# Schematic_tema_tsc_v23.net
KiCad netlist of a schematic drawn in EAGLE
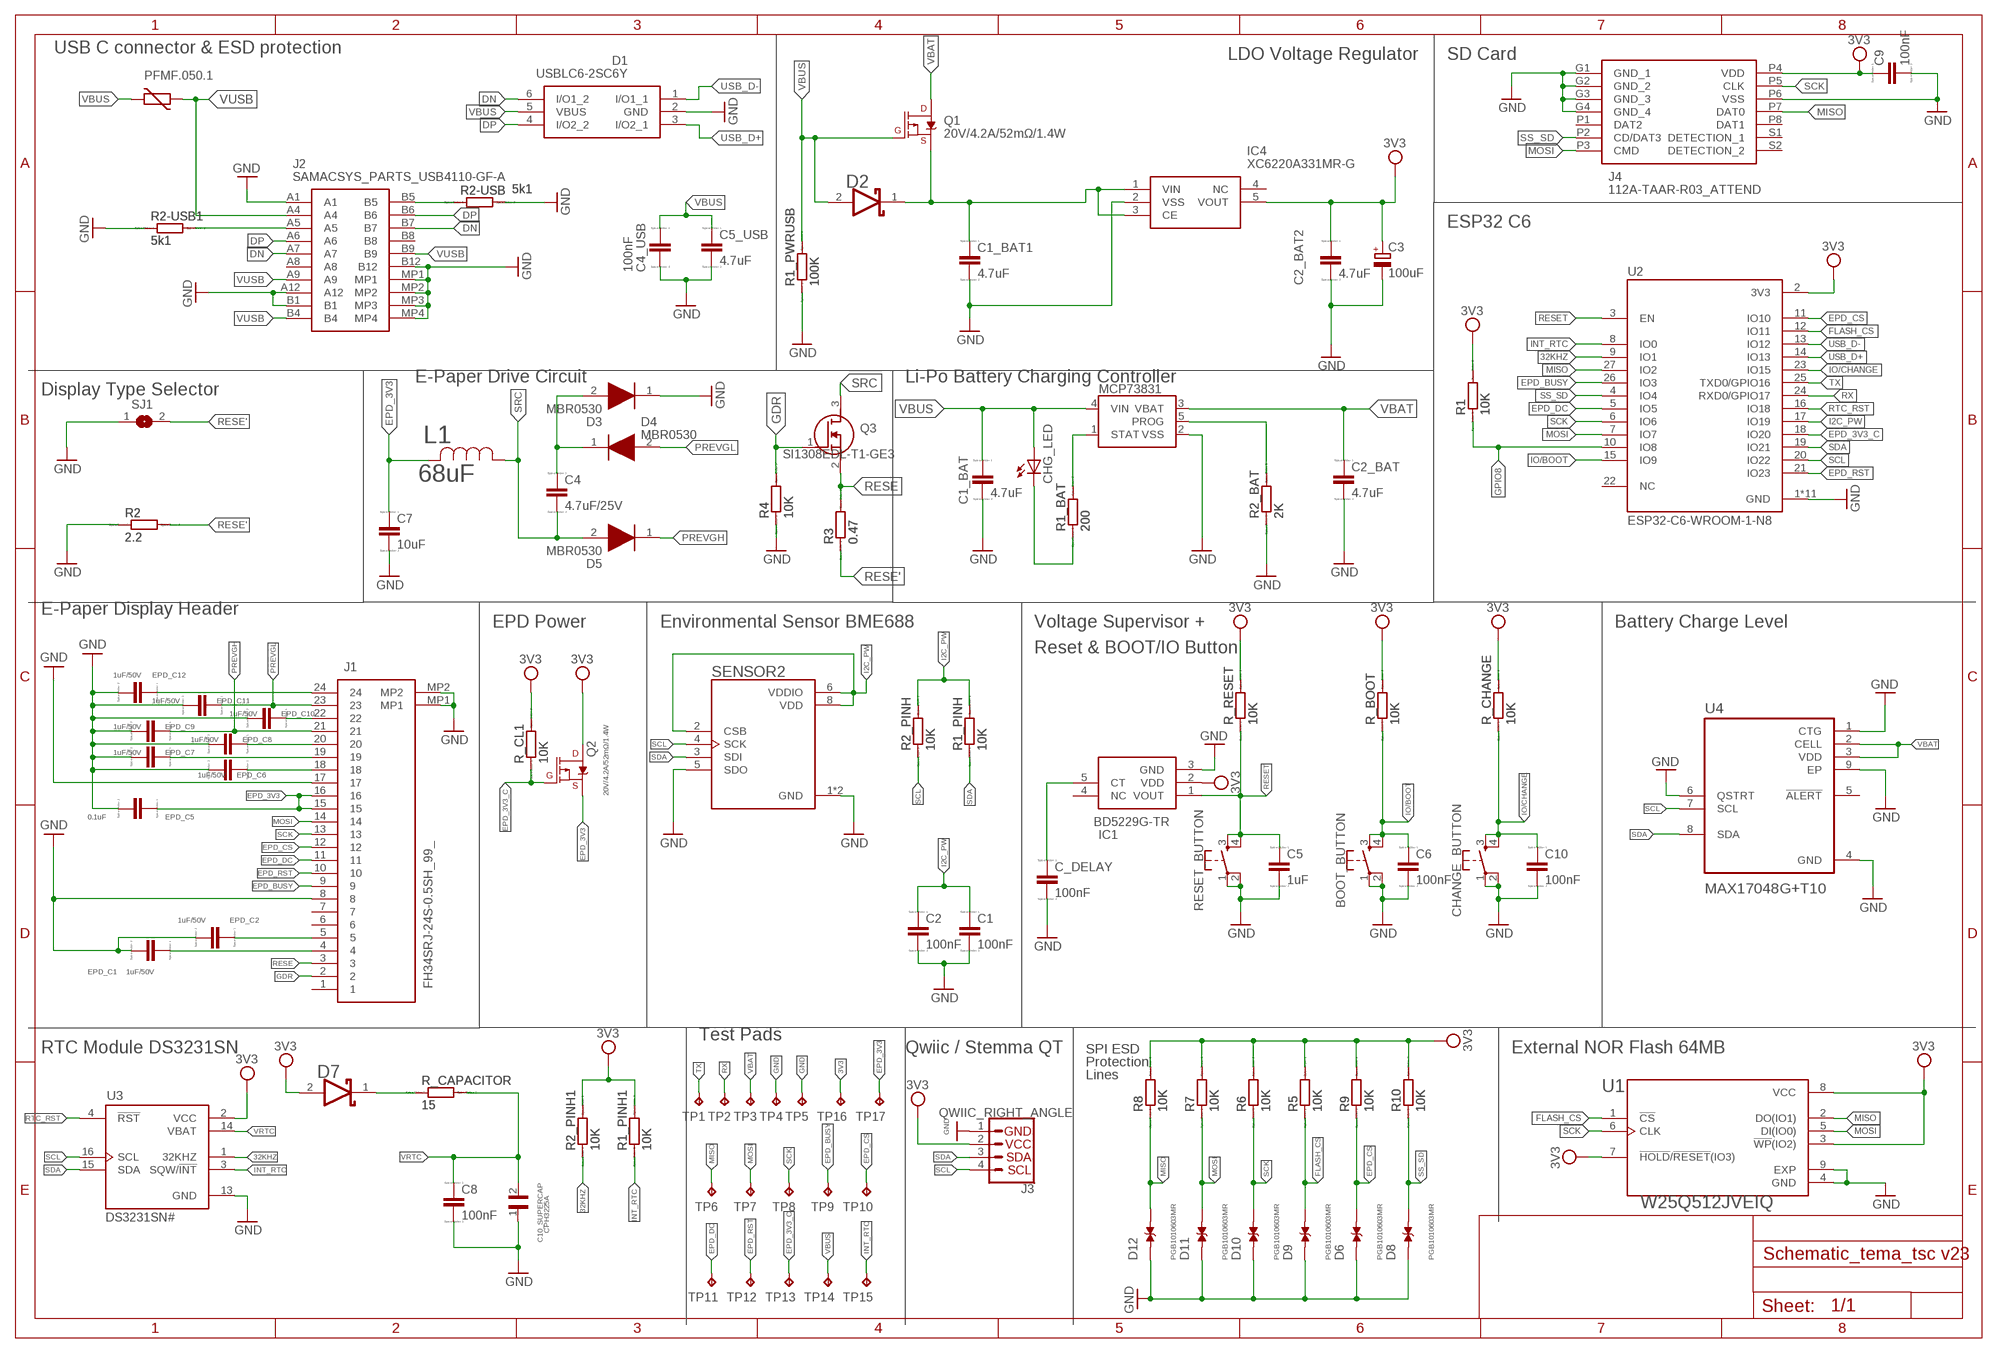
[diagram p0: schematic, sheet 1]

(export (version "E")
  (design (tool "Eeschema 10.0.6"))
  (components
    (comp (ref "BOOT_BUTTON")
      (value "BUTTON_CUSYOMV1")
      (footprint "eagle-import:MYBUTTON")
      (libsource (lib "eagle-import") (part "BUTTON_CUSYOMV1"))
    )
    (comp (ref "C1")
      (value "100nF")
      (footprint "eagle-import:EAGLE-LTSPICE_C0402")
      (libsource (lib "eagle-import") (part "EAGLE-LTSPICE_CC0402"))
    )
    (comp (ref "C1_BAT")
      (value "4.7uF")
      (footprint "eagle-import:EAGLE-LTSPICE_C0402")
      (libsource (lib "eagle-import") (part "EAGLE-LTSPICE_CC0402"))
    )
    (comp (ref "C1_BAT1")
      (value "4.7uF")
      (footprint "eagle-import:EAGLE-LTSPICE_C0402")
      (libsource (lib "eagle-import") (part "EAGLE-LTSPICE_CC0402"))
    )
    (comp (ref "C2")
      (value "100nF")
      (footprint "eagle-import:EAGLE-LTSPICE_C0402")
      (libsource (lib "eagle-import") (part "EAGLE-LTSPICE_CC0402"))
    )
    (comp (ref "C2_BAT")
      (value "4.7uF")
      (footprint "eagle-import:EAGLE-LTSPICE_C0402")
      (libsource (lib "eagle-import") (part "EAGLE-LTSPICE_CC0402"))
    )
    (comp (ref "C2_BAT2")
      (value "4.7uF")
      (footprint "eagle-import:EAGLE-LTSPICE_C0402")
      (libsource (lib "eagle-import") (part "EAGLE-LTSPICE_CC0402"))
    )
    (comp (ref "C3")
      (value "100uF")
      (footprint "eagle-import:RCL_CT3528")
      (libsource (lib "eagle-import") (part "RCL_CPOL-EUCT3528"))
    )
    (comp (ref "C4")
      (value "4.7uF/25V")
      (footprint "eagle-import:EAGLE-LTSPICE_C0402")
      (libsource (lib "eagle-import") (part "EAGLE-LTSPICE_CC0402"))
    )
    (comp (ref "C4_USB")
      (value "100nF")
      (footprint "eagle-import:EAGLE-LTSPICE_C0402")
      (libsource (lib "eagle-import") (part "EAGLE-LTSPICE_CC0402"))
    )
    (comp (ref "C5")
      (value "1uF")
      (footprint "eagle-import:EAGLE-LTSPICE_C0402")
      (libsource (lib "eagle-import") (part "EAGLE-LTSPICE_CC0402"))
    )
    (comp (ref "C5_USB")
      (value "4.7uF")
      (footprint "eagle-import:EAGLE-LTSPICE_C0402")
      (libsource (lib "eagle-import") (part "EAGLE-LTSPICE_CC0402"))
    )
    (comp (ref "C6")
      (value "100nF")
      (footprint "eagle-import:EAGLE-LTSPICE_C0402")
      (libsource (lib "eagle-import") (part "EAGLE-LTSPICE_CC0402"))
    )
    (comp (ref "C7")
      (value "10uF")
      (footprint "eagle-import:EAGLE-LTSPICE_C0402")
      (libsource (lib "eagle-import") (part "EAGLE-LTSPICE_CC0402"))
    )
    (comp (ref "C8")
      (value "100nF")
      (footprint "eagle-import:EAGLE-LTSPICE_C0402")
      (libsource (lib "eagle-import") (part "EAGLE-LTSPICE_CC0402"))
    )
    (comp (ref "C9")
      (value "100nF")
      (footprint "eagle-import:EAGLE-LTSPICE_C0402")
      (libsource (lib "eagle-import") (part "EAGLE-LTSPICE_CC0402"))
    )
    (comp (ref "C10")
      (value "100nF")
      (footprint "eagle-import:EAGLE-LTSPICE_C0402")
      (libsource (lib "eagle-import") (part "EAGLE-LTSPICE_CC0402"))
    )
    (comp (ref "C10_SUPERCAP")
      (value "CPH3225A")
      (footprint "eagle-import:CAPCP3225X100N")
      (fields (field (name "MF") "Seiko Instruments"))
      (libsource (lib "eagle-import") (part "CPH3225A"))
    )
    (comp (ref "CHANGE_BUTTON")
      (value "BUTTON_CUSYOMV1")
      (footprint "eagle-import:MYBUTTON")
      (libsource (lib "eagle-import") (part "BUTTON_CUSYOMV1"))
    )
    (comp (ref "CHG_LED")
      (value "ADAFRUIT_LEDCHIP-LED0603")
      (footprint "eagle-import:ADAFRUIT_CHIP-LED0603")
      (libsource (lib "eagle-import") (part "ADAFRUIT_LEDCHIP-LED0603"))
    )
    (comp (ref "C_DELAY")
      (value "100nF")
      (footprint "eagle-import:EAGLE-LTSPICE_C0402")
      (libsource (lib "eagle-import") (part "EAGLE-LTSPICE_CC0402"))
    )
    (comp (ref "D1")
      (value "USBLC6-2SC6Y")
      (footprint "eagle-import:SOT95P280X145-6N")
      (fields (field (name "MF") "STMicroelectronics"))
      (libsource (lib "eagle-import") (part "USBLC6-2SC6Y"))
    )
    (comp (ref "D2")
      (value "ESP32_WROVER_AVX---SD0805S020S1R0_AVX_SD0805S020S1R0_0_0AVX_SD0805S020S1R0_0_0")
      (footprint "eagle-import:ESP32_WROVER_AVX---SD0805S020S1R0_AVX_SD0805S020S1R0_0")
      (fields
        (field (name "DIGIKEY_PART_NUMBER") "478-7800-1-ND")
        (field (name "MF") "AVX")
        (field (name "MOUSER_PART_NUMBER") "581-SD0805S020S1R0")
      )
      (libsource (lib "eagle-import") (part "ESP32_WROVER_AVX---SD0805S020S1R0_AVX_SD0805S020S1R0_0_0AVX_SD0805S020S1R0_0_0"))
    )
    (comp (ref "D3")
      (value "MBR0530")
      (footprint "eagle-import:SOD3716X135N")
      (fields (field (name "MF") "ON Semiconductor"))
      (libsource (lib "eagle-import") (part "MBR0530"))
    )
    (comp (ref "D4")
      (value "MBR0530")
      (footprint "eagle-import:SOD3716X135N")
      (fields (field (name "MF") "ON Semiconductor"))
      (libsource (lib "eagle-import") (part "MBR0530"))
    )
    (comp (ref "D5")
      (value "MBR0530")
      (footprint "eagle-import:SOD3716X135N")
      (fields (field (name "MF") "ON Semiconductor"))
      (libsource (lib "eagle-import") (part "MBR0530"))
    )
    (comp (ref "D6")
      (value "PGB1010603MR")
      (footprint "eagle-import:DIOC1608X36N")
      (fields (field (name "MF") "Littelfuse Inc."))
      (libsource (lib "eagle-import") (part "PGB1010603MR"))
    )
    (comp (ref "D7")
      (value "ESP32_WROVER_AVX---SD0805S020S1R0_AVX_SD0805S020S1R0_0_0AVX_SD0805S020S1R0_0_0")
      (footprint "eagle-import:ESP32_WROVER_AVX---SD0805S020S1R0_AVX_SD0805S020S1R0_0")
      (fields
        (field (name "DIGIKEY_PART_NUMBER") "478-7800-1-ND")
        (field (name "MF") "AVX")
        (field (name "MOUSER_PART_NUMBER") "581-SD0805S020S1R0")
      )
      (libsource (lib "eagle-import") (part "ESP32_WROVER_AVX---SD0805S020S1R0_AVX_SD0805S020S1R0_0_0AVX_SD0805S020S1R0_0_0"))
    )
    (comp (ref "D8")
      (value "PGB1010603MR")
      (footprint "eagle-import:DIOC1608X36N")
      (fields (field (name "MF") "Littelfuse Inc."))
      (libsource (lib "eagle-import") (part "PGB1010603MR"))
    )
    (comp (ref "D9")
      (value "PGB1010603MR")
      (footprint "eagle-import:DIOC1608X36N")
      (fields (field (name "MF") "Littelfuse Inc."))
      (libsource (lib "eagle-import") (part "PGB1010603MR"))
    )
    (comp (ref "D10")
      (value "PGB1010603MR")
      (footprint "eagle-import:DIOC1608X36N")
      (fields (field (name "MF") "Littelfuse Inc."))
      (libsource (lib "eagle-import") (part "PGB1010603MR"))
    )
    (comp (ref "D11")
      (value "PGB1010603MR")
      (footprint "eagle-import:DIOC1608X36N")
      (fields (field (name "MF") "Littelfuse Inc."))
      (libsource (lib "eagle-import") (part "PGB1010603MR"))
    )
    (comp (ref "D12")
      (value "PGB1010603MR")
      (footprint "eagle-import:DIOC1608X36N")
      (fields (field (name "MF") "Littelfuse Inc."))
      (libsource (lib "eagle-import") (part "PGB1010603MR"))
    )
    (comp (ref "EPD_C1")
      (value "1uF/50V")
      (footprint "eagle-import:EAGLE-LTSPICE_C0402")
      (libsource (lib "eagle-import") (part "EAGLE-LTSPICE_CC0402"))
    )
    (comp (ref "EPD_C2")
      (value "1uF/50V")
      (footprint "eagle-import:EAGLE-LTSPICE_C0402")
      (libsource (lib "eagle-import") (part "EAGLE-LTSPICE_CC0402"))
    )
    (comp (ref "EPD_C5")
      (value "0.1uF")
      (footprint "eagle-import:EAGLE-LTSPICE_C0402")
      (libsource (lib "eagle-import") (part "EAGLE-LTSPICE_CC0402"))
    )
    (comp (ref "EPD_C6")
      (value "1uF/50V")
      (footprint "eagle-import:EAGLE-LTSPICE_C0402")
      (libsource (lib "eagle-import") (part "EAGLE-LTSPICE_CC0402"))
    )
    (comp (ref "EPD_C7")
      (value "1uF/50V")
      (footprint "eagle-import:EAGLE-LTSPICE_C0402")
      (libsource (lib "eagle-import") (part "EAGLE-LTSPICE_CC0402"))
    )
    (comp (ref "EPD_C8")
      (value "1uF/50V")
      (footprint "eagle-import:EAGLE-LTSPICE_C0402")
      (libsource (lib "eagle-import") (part "EAGLE-LTSPICE_CC0402"))
    )
    (comp (ref "EPD_C9")
      (value "1uF/50V")
      (footprint "eagle-import:EAGLE-LTSPICE_C0402")
      (libsource (lib "eagle-import") (part "EAGLE-LTSPICE_CC0402"))
    )
    (comp (ref "EPD_C10")
      (value "1uF/50V")
      (footprint "eagle-import:EAGLE-LTSPICE_C0402")
      (libsource (lib "eagle-import") (part "EAGLE-LTSPICE_CC0402"))
    )
    (comp (ref "EPD_C11")
      (value "1uF/50V")
      (footprint "eagle-import:EAGLE-LTSPICE_C0402")
      (libsource (lib "eagle-import") (part "EAGLE-LTSPICE_CC0402"))
    )
    (comp (ref "EPD_C12")
      (value "1uF/50V")
      (footprint "eagle-import:EAGLE-LTSPICE_C0402")
      (libsource (lib "eagle-import") (part "EAGLE-LTSPICE_CC0402"))
    )
    (comp (ref "IC1")
      (value "BD5229G-TR")
      (footprint "eagle-import:SOT95P280X125-5N")
      (fields (field (name "MOUSER_PART_NUMBER") "755-BD5229G-TR"))
      (libsource (lib "eagle-import") (part "BD5229G-TR"))
    )
    (comp (ref "IC4")
      (value "XC6220A331MR-G")
      (footprint "eagle-import:SOT95P280X120-5N")
      (fields (field (name "MOUSER_PART_NUMBER") "865-XC6220A331MR-G"))
      (libsource (lib "eagle-import") (part "XC6220A331MR-G"))
    )
    (comp (ref "J1")
      (value "FH34SRJ-24S-0.5SH_99_")
      (footprint "eagle-import:FH34SRJ24S05SH99")
      (fields
        (field (name "MANUFACTURER_PART_NUMBER") "FH34SRJ-24S-0.5SH(99)")
        (field (name "MOUSER_PART_NUMBER") "798-FH34SRJ24S05SH99")
      )
      (libsource (lib "eagle-import") (part "FH34SRJ-24S-0.5SH_99_"))
    )
    (comp (ref "J2")
      (value "SAMACSYS_PARTS_USB4110-GF-A")
      (footprint "eagle-import:SAMACSYS_PARTS_USB4110GFA")
      (fields
        (field (name "MANUFACTURER_PART_NUMBER") "USB4110-GF-A")
        (field (name "MOUSER_PART_NUMBER") "640-USB4110-GF-A")
      )
      (libsource (lib "eagle-import") (part "SAMACSYS_PARTS_USB4110-GF-A"))
    )
    (comp (ref "J3")
      (value "QWIIC_RIGHT_ANGLE")
      (footprint "eagle-import:JST04_1MM_RA")
      (libsource (lib "eagle-import") (part "QWIIC_CONNECTORJS-1MM"))
    )
    (comp (ref "J4")
      (value "112A-TAAR-R03_ATTEND")
      (footprint "eagle-import:112ATAARR03ATTEND")
      (fields (field (name "MANUFACTURER_PART_NUMBER") "112A-TAAR-R03 ATTEND"))
      (libsource (lib "eagle-import") (part "112A-TAAR-R03_ATTEND"))
    )
    (comp (ref "L1")
      (value "68uF")
      (footprint "eagle-import:IND_4828-WE-TPC_WRE")
      (fields
        (field (name "MANUFACTURER_PART_NUMBER") "744043680")
        (field (name "COPYRIGHT") "Copyright (C) 2024 Ultra Librarian. All rights reserved.")
      )
      (libsource (lib "eagle-import") (part "744043680IND_4828-WE-TPC_WRE"))
    )
    (comp (ref "MCP73831")
      (value "ESP32_WROVER_SPARKFUN-IC-POWER_MCP73831")
      (footprint "eagle-import:ESP32_WROVER_SPARKFUN-IC-POWER_SOT23-5")
      (libsource (lib "eagle-import") (part "ESP32_WROVER_SPARKFUN-IC-POWER_MCP73831"))
    )
    (comp (ref "PFMF.050.1")
      (value "ESP32C6_VARISTORCN1812")
      (footprint "eagle-import:ESP32C6_VARISTOR_CT_CN1812")
      (libsource (lib "eagle-import") (part "ESP32C6_VARISTORCN1812"))
    )
    (comp (ref "Q1")
      (value "20V/4.2A/52mΩ/1.4W")
      (footprint "eagle-import:ESP32_WROVER_SPARKFUN-DISCRETESEMI_SOT23-3")
      (libsource (lib "eagle-import") (part "ESP32_WROVER_SPARKFUN-DISCRETESEMI_MOSFET_PCH-DMG2305UX-7"))
    )
    (comp (ref "Q2")
      (value "20V/4.2A/52mΩ/1.4W")
      (footprint "eagle-import:ESP32_WROVER_SPARKFUN-DISCRETESEMI_SOT23-3")
      (libsource (lib "eagle-import") (part "ESP32_WROVER_SPARKFUN-DISCRETESEMI_MOSFET_PCH-DMG2305UX-7"))
    )
    (comp (ref "Q3")
      (value "SI1308EDL-T1-GE3")
      (footprint "eagle-import:SOT65P210X110-3N")
      (fields (field (name "MF") "Vishay Siliconix"))
      (libsource (lib "eagle-import") (part "SI1308EDL-T1-GE3"))
    )
    (comp (ref "R1")
      (value "10K")
      (footprint "eagle-import:ESP32_WROVER_EAGLE-LTSPICE_R0402")
      (libsource (lib "eagle-import") (part "ESP32_WROVER_EAGLE-LTSPICE_RR0402"))
    )
    (comp (ref "R1_BAT")
      (value "200")
      (footprint "eagle-import:ESP32_WROVER_EAGLE-LTSPICE_R0402")
      (libsource (lib "eagle-import") (part "ESP32_WROVER_EAGLE-LTSPICE_RR0402"))
    )
    (comp (ref "R1_PINH")
      (value "10K")
      (footprint "eagle-import:ESP32_WROVER_EAGLE-LTSPICE_R0402")
      (libsource (lib "eagle-import") (part "ESP32_WROVER_EAGLE-LTSPICE_RR0402"))
    )
    (comp (ref "R1_PINH1")
      (value "10K")
      (footprint "eagle-import:ESP32_WROVER_EAGLE-LTSPICE_R0402")
      (libsource (lib "eagle-import") (part "ESP32_WROVER_EAGLE-LTSPICE_RR0402"))
    )
    (comp (ref "R1_PWRUSB")
      (value "100K")
      (footprint "eagle-import:ESP32_WROVER_EAGLE-LTSPICE_R0402")
      (libsource (lib "eagle-import") (part "ESP32_WROVER_EAGLE-LTSPICE_RR0402"))
    )
    (comp (ref "R2")
      (value "2.2")
      (footprint "eagle-import:ESP32_WROVER_EAGLE-LTSPICE_R0402")
      (libsource (lib "eagle-import") (part "ESP32_WROVER_EAGLE-LTSPICE_RR0402"))
    )
    (comp (ref "R2-USB")
      (value "5k1")
      (footprint "eagle-import:ESP32_WROVER_EAGLE-LTSPICE_R0402")
      (libsource (lib "eagle-import") (part "ESP32_WROVER_EAGLE-LTSPICE_RR0402"))
    )
    (comp (ref "R2-USB1")
      (value "5k1")
      (footprint "eagle-import:ESP32_WROVER_EAGLE-LTSPICE_R0402")
      (libsource (lib "eagle-import") (part "ESP32_WROVER_EAGLE-LTSPICE_RR0402"))
    )
    (comp (ref "R2_BAT")
      (value "2K")
      (footprint "eagle-import:ESP32_WROVER_EAGLE-LTSPICE_R0402")
      (libsource (lib "eagle-import") (part "ESP32_WROVER_EAGLE-LTSPICE_RR0402"))
    )
    (comp (ref "R2_PINH")
      (value "10K")
      (footprint "eagle-import:ESP32_WROVER_EAGLE-LTSPICE_R0402")
      (libsource (lib "eagle-import") (part "ESP32_WROVER_EAGLE-LTSPICE_RR0402"))
    )
    (comp (ref "R2_PINH1")
      (value "10K")
      (footprint "eagle-import:ESP32_WROVER_EAGLE-LTSPICE_R0402")
      (libsource (lib "eagle-import") (part "ESP32_WROVER_EAGLE-LTSPICE_RR0402"))
    )
    (comp (ref "R3")
      (value "0.47")
      (footprint "eagle-import:ESP32_WROVER_EAGLE-LTSPICE_R0402")
      (libsource (lib "eagle-import") (part "ESP32_WROVER_EAGLE-LTSPICE_RR0402"))
    )
    (comp (ref "R4")
      (value "10K")
      (footprint "eagle-import:ESP32_WROVER_EAGLE-LTSPICE_R0402")
      (libsource (lib "eagle-import") (part "ESP32_WROVER_EAGLE-LTSPICE_RR0402"))
    )
    (comp (ref "R5")
      (value "10K")
      (footprint "eagle-import:ESP32_WROVER_EAGLE-LTSPICE_R0402")
      (libsource (lib "eagle-import") (part "ESP32_WROVER_EAGLE-LTSPICE_RR0402"))
    )
    (comp (ref "R6")
      (value "10K")
      (footprint "eagle-import:ESP32_WROVER_EAGLE-LTSPICE_R0402")
      (libsource (lib "eagle-import") (part "ESP32_WROVER_EAGLE-LTSPICE_RR0402"))
    )
    (comp (ref "R7")
      (value "10K")
      (footprint "eagle-import:ESP32_WROVER_EAGLE-LTSPICE_R0402")
      (libsource (lib "eagle-import") (part "ESP32_WROVER_EAGLE-LTSPICE_RR0402"))
    )
    (comp (ref "R8")
      (value "10K")
      (footprint "eagle-import:ESP32_WROVER_EAGLE-LTSPICE_R0402")
      (libsource (lib "eagle-import") (part "ESP32_WROVER_EAGLE-LTSPICE_RR0402"))
    )
    (comp (ref "R9")
      (value "10K")
      (footprint "eagle-import:ESP32_WROVER_EAGLE-LTSPICE_R0402")
      (libsource (lib "eagle-import") (part "ESP32_WROVER_EAGLE-LTSPICE_RR0402"))
    )
    (comp (ref "R10")
      (value "10K")
      (footprint "eagle-import:ESP32_WROVER_EAGLE-LTSPICE_R0402")
      (libsource (lib "eagle-import") (part "ESP32_WROVER_EAGLE-LTSPICE_RR0402"))
    )
    (comp (ref "RESET_BUTTON")
      (value "BUTTON_CUSYOMV1")
      (footprint "eagle-import:MYBUTTON")
      (libsource (lib "eagle-import") (part "BUTTON_CUSYOMV1"))
    )
    (comp (ref "R_BOOT")
      (value "10K")
      (footprint "eagle-import:ESP32_WROVER_EAGLE-LTSPICE_R0402")
      (libsource (lib "eagle-import") (part "ESP32_WROVER_EAGLE-LTSPICE_RR0402"))
    )
    (comp (ref "R_CAPACITOR")
      (value "15")
      (footprint "eagle-import:ESP32_WROVER_EAGLE-LTSPICE_R0402")
      (libsource (lib "eagle-import") (part "ESP32_WROVER_EAGLE-LTSPICE_RR0402"))
    )
    (comp (ref "R_CHANGE")
      (value "10K")
      (footprint "eagle-import:ESP32_WROVER_EAGLE-LTSPICE_R0402")
      (libsource (lib "eagle-import") (part "ESP32_WROVER_EAGLE-LTSPICE_RR0402"))
    )
    (comp (ref "R_CL1")
      (value "10K")
      (footprint "eagle-import:ESP32_WROVER_EAGLE-LTSPICE_R0402")
      (libsource (lib "eagle-import") (part "ESP32_WROVER_EAGLE-LTSPICE_RR0402"))
    )
    (comp (ref "R_RESET")
      (value "10K")
      (footprint "eagle-import:ESP32_WROVER_EAGLE-LTSPICE_R0402")
      (libsource (lib "eagle-import") (part "ESP32_WROVER_EAGLE-LTSPICE_RR0402"))
    )
    (comp (ref "SENSOR2")
      (value "ESP32_WROVER_BME680_BME680")
      (footprint "eagle-import:ESP32_WROVER_BME680_PSON80P300X300X100-8N")
      (fields (field (name "MF") "Bosch Sensortec") (field (name "MP") "BME680"))
      (libsource (lib "eagle-import") (part "ESP32_WROVER_BME680_BME680"))
    )
    (comp (ref "SJ1") (value "SJ") (footprint "eagle-import:SJ") (libsource (lib "eagle-import") (part "SJ")))
    (comp (ref "TP1")
      (value "TPTP20R")
      (footprint "eagle-import:TP20R")
      (libsource (lib "eagle-import") (part "TPTP20R"))
    )
    (comp (ref "TP2")
      (value "TPTP20R")
      (footprint "eagle-import:TP20R")
      (libsource (lib "eagle-import") (part "TPTP20R"))
    )
    (comp (ref "TP3")
      (value "TPTP20R")
      (footprint "eagle-import:TP20R")
      (libsource (lib "eagle-import") (part "TPTP20R"))
    )
    (comp (ref "TP4")
      (value "TPTP20R")
      (footprint "eagle-import:TP20R")
      (libsource (lib "eagle-import") (part "TPTP20R"))
    )
    (comp (ref "TP5")
      (value "TPTP20R")
      (footprint "eagle-import:TP20R")
      (libsource (lib "eagle-import") (part "TPTP20R"))
    )
    (comp (ref "TP6")
      (value "TPTP20R")
      (footprint "eagle-import:TP20R")
      (libsource (lib "eagle-import") (part "TPTP20R"))
    )
    (comp (ref "TP7")
      (value "TPTP20R")
      (footprint "eagle-import:TP20R")
      (libsource (lib "eagle-import") (part "TPTP20R"))
    )
    (comp (ref "TP8")
      (value "TPTP20R")
      (footprint "eagle-import:TP20R")
      (libsource (lib "eagle-import") (part "TPTP20R"))
    )
    (comp (ref "TP9")
      (value "TPTP20R")
      (footprint "eagle-import:TP20R")
      (libsource (lib "eagle-import") (part "TPTP20R"))
    )
    (comp (ref "TP10")
      (value "TPTP20R")
      (footprint "eagle-import:TP20R")
      (libsource (lib "eagle-import") (part "TPTP20R"))
    )
    (comp (ref "TP11")
      (value "TPTP20R")
      (footprint "eagle-import:TP20R")
      (libsource (lib "eagle-import") (part "TPTP20R"))
    )
    (comp (ref "TP12")
      (value "TPTP20R")
      (footprint "eagle-import:TP20R")
      (libsource (lib "eagle-import") (part "TPTP20R"))
    )
    (comp (ref "TP13")
      (value "TPTP20R")
      (footprint "eagle-import:TP20R")
      (libsource (lib "eagle-import") (part "TPTP20R"))
    )
    (comp (ref "TP14")
      (value "TPTP20R")
      (footprint "eagle-import:TP20R")
      (libsource (lib "eagle-import") (part "TPTP20R"))
    )
    (comp (ref "TP15")
      (value "TPTP20R")
      (footprint "eagle-import:TP20R")
      (libsource (lib "eagle-import") (part "TPTP20R"))
    )
    (comp (ref "TP16")
      (value "TPTP20R")
      (footprint "eagle-import:TP20R")
      (libsource (lib "eagle-import") (part "TPTP20R"))
    )
    (comp (ref "TP17")
      (value "TPTP20R")
      (footprint "eagle-import:TP20R")
      (libsource (lib "eagle-import") (part "TPTP20R"))
    )
    (comp (ref "U1")
      (value "W25Q512JVEIQ")
      (footprint "eagle-import:SON127P600X800X80-9N")
      (fields (field (name "MF") "Winbond Electronics"))
      (libsource (lib "eagle-import") (part "W25Q512JVEIQ"))
    )
    (comp (ref "U2")
      (value "ESP32-C6-WROOM-1-N8")
      (footprint "eagle-import:XCVR_ESP32-C6-WROOM-1-N8")
      (fields (field (name "MF") "Espressif Systems"))
      (libsource (lib "eagle-import") (part "ESP32-C6-WROOM-1-N8"))
    )
    (comp (ref "U3")
      (value "DS3231SN#")
      (footprint "eagle-import:SOIC127P1032X265-16N")
      (fields (field (name "MF") "Analog Devices"))
      (libsource (lib "eagle-import") (part "DS3231SN#"))
    )
    (comp (ref "U4")
      (value "MAX17048G+T10")
      (footprint "eagle-import:SON50P200X200X80-9N")
      (fields (field (name "MF") "Analog Devices"))
      (libsource (lib "eagle-import") (part "MAX17048G+T10"))
    )
  )
  (nets
    (net (code "1") (name "3V3") (class "Default")
      (node (ref "C2_BAT2") (pin "1") (pinfunction "1_1") (pintype "passive"))
      (node (ref "C3") (pin "+") (pinfunction "+_+") (pintype "passive"))
      (node (ref "C9") (pin "1") (pinfunction "1_1") (pintype "passive"))
      (node (ref "D7") (pin "2") (pinfunction "ANODE_2") (pintype "bidirectional"))
      (node (ref "IC1") (pin "2") (pinfunction "VDD_2") (pintype "bidirectional"))
      (node (ref "IC4") (pin "5") (pinfunction "VOUT_5") (pintype "bidirectional"))
      (node (ref "J3") (pin "2") (pinfunction "2_2") (pintype "power_in"))
      (node (ref "J4") (pin "P4") (pinfunction "VDD_P4") (pintype "bidirectional"))
      (node (ref "Q2") (pin "3") (pinfunction "D_3") (pintype "bidirectional"))
      (node (ref "R1") (pin "2") (pinfunction "2_2") (pintype "passive"))
      (node (ref "R10") (pin "2") (pinfunction "2_2") (pintype "passive"))
      (node (ref "R1_PINH1") (pin "2") (pinfunction "2_2") (pintype "passive"))
      (node (ref "R2_PINH1") (pin "2") (pinfunction "2_2") (pintype "passive"))
      (node (ref "R5") (pin "2") (pinfunction "2_2") (pintype "passive"))
      (node (ref "R6") (pin "2") (pinfunction "2_2") (pintype "passive"))
      (node (ref "R7") (pin "2") (pinfunction "2_2") (pintype "passive"))
      (node (ref "R8") (pin "2") (pinfunction "2_2") (pintype "passive"))
      (node (ref "R9") (pin "2") (pinfunction "2_2") (pintype "passive"))
      (node (ref "R_BOOT") (pin "2") (pinfunction "2_2") (pintype "passive"))
      (node (ref "R_CHANGE") (pin "2") (pinfunction "2_2") (pintype "passive"))
      (node (ref "R_CL1") (pin "2") (pinfunction "2_2") (pintype "passive"))
      (node (ref "R_RESET") (pin "2") (pinfunction "2_2") (pintype "passive"))
      (node (ref "TP16") (pin "TP") (pinfunction "TP_TP") (pintype "input"))
      (node (ref "U1") (pin "3") (pinfunction "~{WP}(IO2)_3") (pintype "bidirectional"))
      (node (ref "U1") (pin "7") (pinfunction "~{HOLD}/~{RESET}(IO3)_7") (pintype "bidirectional"))
      (node (ref "U1") (pin "8") (pinfunction "VCC_8") (pintype "power_in"))
      (node (ref "U2") (pin "2") (pinfunction "3V3_2") (pintype "power_in"))
      (node (ref "U3") (pin "2") (pinfunction "VCC_2") (pintype "power_in"))
    )
    (net (code "2") (name "32KHZ") (class "Default")
      (node (ref "R2_PINH1") (pin "1") (pinfunction "1_1") (pintype "passive"))
      (node (ref "U2") (pin "9") (pinfunction "IO1_9") (pintype "bidirectional"))
      (node (ref "U3") (pin "1") (pinfunction "32KHZ_1") (pintype "output"))
    )
    (net (code "3") (name "DN") (class "Default")
      (node (ref "D1") (pin "6") (pinfunction "I/O1_2_6") (pintype "bidirectional"))
      (node (ref "J2") (pin "A7") (pinfunction "A7_A7") (pintype "bidirectional"))
      (node (ref "J2") (pin "B7") (pinfunction "B7_B7") (pintype "bidirectional"))
    )
    (net (code "4") (name "DP") (class "Default")
      (node (ref "D1") (pin "4") (pinfunction "I/O2_2_4") (pintype "bidirectional"))
      (node (ref "J2") (pin "A6") (pinfunction "A6_A6") (pintype "bidirectional"))
      (node (ref "J2") (pin "B6") (pinfunction "B6_B6") (pintype "bidirectional"))
    )
    (net (code "5") (name "EPD_3V3") (class "Default")
      (node (ref "C7") (pin "1") (pinfunction "1_1") (pintype "passive"))
      (node (ref "EPD_C5") (pin "1") (pinfunction "1_1") (pintype "passive"))
      (node (ref "J1") (pin "15") (pinfunction "15_15") (pintype "bidirectional"))
      (node (ref "J1") (pin "16") (pinfunction "16_16") (pintype "bidirectional"))
      (node (ref "L1") (pin "2") (pinfunction "2_2") (pintype "passive"))
      (node (ref "Q2") (pin "2") (pinfunction "S_2") (pintype "bidirectional"))
      (node (ref "TP17") (pin "TP") (pinfunction "TP_TP") (pintype "input"))
    )
    (net (code "6") (name "EPD_3V3_C") (class "Default")
      (node (ref "Q2") (pin "1") (pinfunction "G_1") (pintype "bidirectional"))
      (node (ref "R_CL1") (pin "1") (pinfunction "1_1") (pintype "passive"))
      (node (ref "TP13") (pin "TP") (pinfunction "TP_TP") (pintype "input"))
      (node (ref "U2") (pin "18") (pinfunction "IO20_18") (pintype "bidirectional"))
    )
    (net (code "7") (name "EPD_BUSY") (class "Default")
      (node (ref "J1") (pin "9") (pinfunction "9_9") (pintype "bidirectional"))
      (node (ref "TP9") (pin "TP") (pinfunction "TP_TP") (pintype "input"))
      (node (ref "U2") (pin "26") (pinfunction "IO3_26") (pintype "bidirectional"))
    )
    (net (code "8") (name "EPD_CS") (class "Default")
      (node (ref "D6") (pin "2") (pinfunction "2_2") (pintype "passive"))
      (node (ref "J1") (pin "12") (pinfunction "12_12") (pintype "bidirectional"))
      (node (ref "R9") (pin "1") (pinfunction "1_1") (pintype "passive"))
      (node (ref "TP10") (pin "TP") (pinfunction "TP_TP") (pintype "input"))
      (node (ref "U2") (pin "11") (pinfunction "IO10_11") (pintype "bidirectional"))
    )
    (net (code "9") (name "EPD_DC") (class "Default")
      (node (ref "J1") (pin "11") (pinfunction "11_11") (pintype "bidirectional"))
      (node (ref "TP11") (pin "TP") (pinfunction "TP_TP") (pintype "input"))
      (node (ref "U2") (pin "5") (pinfunction "IO5_5") (pintype "bidirectional"))
    )
    (net (code "10") (name "EPD_RST") (class "Default")
      (node (ref "J1") (pin "10") (pinfunction "10_10") (pintype "bidirectional"))
      (node (ref "TP12") (pin "TP") (pinfunction "TP_TP") (pintype "input"))
      (node (ref "U2") (pin "21") (pinfunction "IO23_21") (pintype "bidirectional"))
    )
    (net (code "11") (name "FLASH_CS") (class "Default")
      (node (ref "D9") (pin "2") (pinfunction "2_2") (pintype "passive"))
      (node (ref "R5") (pin "1") (pinfunction "1_1") (pintype "passive"))
      (node (ref "U1") (pin "1") (pinfunction "~{CS}_1") (pintype "input"))
      (node (ref "U2") (pin "12") (pinfunction "IO11_12") (pintype "bidirectional"))
    )
    (net (code "12") (name "GDR") (class "Default")
      (node (ref "J1") (pin "2") (pinfunction "2_2") (pintype "bidirectional"))
      (node (ref "Q3") (pin "1") (pinfunction "G_1") (pintype "bidirectional"))
      (node (ref "R4") (pin "2") (pinfunction "2_2") (pintype "passive"))
    )
    (net (code "13") (name "GND") (class "Default")
      (node (ref "BOOT_BUTTON") (pin "1") (pinfunction "1_1") (pintype "passive"))
      (node (ref "BOOT_BUTTON") (pin "2") (pinfunction "2_2") (pintype "passive"))
      (node (ref "C1") (pin "2") (pinfunction "2_2") (pintype "passive"))
      (node (ref "C10") (pin "2") (pinfunction "2_2") (pintype "passive"))
      (node (ref "C10_SUPERCAP") (pin "1") (pinfunction "1_1") (pintype "passive"))
      (node (ref "C1_BAT") (pin "2") (pinfunction "2_2") (pintype "passive"))
      (node (ref "C1_BAT1") (pin "2") (pinfunction "2_2") (pintype "passive"))
      (node (ref "C2") (pin "2") (pinfunction "2_2") (pintype "passive"))
      (node (ref "C2_BAT") (pin "2") (pinfunction "2_2") (pintype "passive"))
      (node (ref "C2_BAT2") (pin "2") (pinfunction "2_2") (pintype "passive"))
      (node (ref "C3") (pin "-") (pinfunction "-_-") (pintype "passive"))
      (node (ref "C4_USB") (pin "2") (pinfunction "2_2") (pintype "passive"))
      (node (ref "C5") (pin "2") (pinfunction "2_2") (pintype "passive"))
      (node (ref "C5_USB") (pin "2") (pinfunction "2_2") (pintype "passive"))
      (node (ref "C6") (pin "2") (pinfunction "2_2") (pintype "passive"))
      (node (ref "C7") (pin "2") (pinfunction "2_2") (pintype "passive"))
      (node (ref "C8") (pin "2") (pinfunction "2_2") (pintype "passive"))
      (node (ref "C9") (pin "2") (pinfunction "2_2") (pintype "passive"))
      (node (ref "CHANGE_BUTTON") (pin "1") (pinfunction "1_1") (pintype "passive"))
      (node (ref "CHANGE_BUTTON") (pin "2") (pinfunction "2_2") (pintype "passive"))
      (node (ref "C_DELAY") (pin "2") (pinfunction "2_2") (pintype "passive"))
      (node (ref "D1") (pin "2") (pinfunction "GND_2") (pintype "bidirectional"))
      (node (ref "D10") (pin "1") (pinfunction "1_1") (pintype "passive"))
      (node (ref "D11") (pin "1") (pinfunction "1_1") (pintype "passive"))
      (node (ref "D12") (pin "1") (pinfunction "1_1") (pintype "passive"))
      (node (ref "D3") (pin "1") (pinfunction "K_1") (pintype "bidirectional"))
      (node (ref "D6") (pin "1") (pinfunction "1_1") (pintype "passive"))
      (node (ref "D8") (pin "1") (pinfunction "1_1") (pintype "passive"))
      (node (ref "D9") (pin "1") (pinfunction "1_1") (pintype "passive"))
      (node (ref "EPD_C1") (pin "2") (pinfunction "2_2") (pintype "passive"))
      (node (ref "EPD_C10") (pin "2") (pinfunction "2_2") (pintype "passive"))
      (node (ref "EPD_C11") (pin "2") (pinfunction "2_2") (pintype "passive"))
      (node (ref "EPD_C12") (pin "2") (pinfunction "2_2") (pintype "passive"))
      (node (ref "EPD_C2") (pin "2") (pinfunction "2_2") (pintype "passive"))
      (node (ref "EPD_C5") (pin "2") (pinfunction "2_2") (pintype "passive"))
      (node (ref "EPD_C6") (pin "2") (pinfunction "2_2") (pintype "passive"))
      (node (ref "EPD_C7") (pin "2") (pinfunction "2_2") (pintype "passive"))
      (node (ref "EPD_C8") (pin "2") (pinfunction "2_2") (pintype "passive"))
      (node (ref "EPD_C9") (pin "2") (pinfunction "2_2") (pintype "passive"))
      (node (ref "IC1") (pin "3") (pinfunction "GND_3") (pintype "bidirectional"))
      (node (ref "IC4") (pin "2") (pinfunction "VSS_2") (pintype "bidirectional"))
      (node (ref "J1") (pin "17") (pinfunction "17_17") (pintype "bidirectional"))
      (node (ref "J1") (pin "8") (pinfunction "8_8") (pintype "bidirectional"))
      (node (ref "J1") (pin "MP1") (pinfunction "MP1_MP1") (pintype "bidirectional"))
      (node (ref "J1") (pin "MP2") (pinfunction "MP2_MP2") (pintype "bidirectional"))
      (node (ref "J2") (pin "A1") (pinfunction "A1_A1") (pintype "bidirectional"))
      (node (ref "J2") (pin "A12") (pinfunction "A12_A12") (pintype "bidirectional"))
      (node (ref "J2") (pin "B1") (pinfunction "B1_B1") (pintype "bidirectional"))
      (node (ref "J2") (pin "B12") (pinfunction "B12_B12") (pintype "bidirectional"))
      (node (ref "J2") (pin "MP1") (pinfunction "MP1_MP1") (pintype "bidirectional"))
      (node (ref "J2") (pin "MP2") (pinfunction "MP2_MP2") (pintype "bidirectional"))
      (node (ref "J2") (pin "MP3") (pinfunction "MP3_MP3") (pintype "bidirectional"))
      (node (ref "J2") (pin "MP4") (pinfunction "MP4_MP4") (pintype "bidirectional"))
      (node (ref "J3") (pin "1") (pinfunction "1_1") (pintype "power_in"))
      (node (ref "J4") (pin "G1") (pinfunction "GND_1_G1") (pintype "bidirectional"))
      (node (ref "J4") (pin "G2") (pinfunction "GND_2_G2") (pintype "bidirectional"))
      (node (ref "J4") (pin "G3") (pinfunction "GND_3_G3") (pintype "bidirectional"))
      (node (ref "J4") (pin "G4") (pinfunction "GND_4_G4") (pintype "bidirectional"))
      (node (ref "J4") (pin "P6") (pinfunction "VSS_P6") (pintype "bidirectional"))
      (node (ref "MCP73831") (pin "2") (pinfunction "VSS_2") (pintype "power_in"))
      (node (ref "R1_PWRUSB") (pin "1") (pinfunction "1_1") (pintype "passive"))
      (node (ref "R2") (pin "1") (pinfunction "1_1") (pintype "passive"))
      (node (ref "R2-USB") (pin "2") (pinfunction "2_2") (pintype "passive"))
      (node (ref "R2-USB1") (pin "1") (pinfunction "1_1") (pintype "passive"))
      (node (ref "R2_BAT") (pin "1") (pinfunction "1_1") (pintype "passive"))
      (node (ref "R4") (pin "1") (pinfunction "1_1") (pintype "passive"))
      (node (ref "RESET_BUTTON") (pin "1") (pinfunction "1_1") (pintype "passive"))
      (node (ref "RESET_BUTTON") (pin "2") (pinfunction "2_2") (pintype "passive"))
      (node (ref "SENSOR2") (pin "1") (pinfunction "GND_1") (pintype "power_in"))
      (node (ref "SENSOR2") (pin "5") (pinfunction "SDO_5") (pintype "bidirectional"))
      (node (ref "SENSOR2") (pin "7") (pinfunction "GND_7") (pintype "power_in"))
      (node (ref "SJ1") (pin "1") (pinfunction "1_1") (pintype "passive"))
      (node (ref "TP4") (pin "TP") (pinfunction "TP_TP") (pintype "input"))
      (node (ref "TP5") (pin "TP") (pinfunction "TP_TP") (pintype "input"))
      (node (ref "U1") (pin "4") (pinfunction "GND_4") (pintype "power_in"))
      (node (ref "U1") (pin "9") (pinfunction "EXP_9") (pintype "passive"))
      (node (ref "U2") (pin "1") (pinfunction "GND_1") (pintype "power_in"))
      (node (ref "U2") (pin "28") (pinfunction "GND_28") (pintype "power_in"))
      (node (ref "U2") (pin "29_1") (pinfunction "GND_29_1") (pintype "power_in"))
      (node (ref "U2") (pin "29_2") (pinfunction "GND_29_2") (pintype "power_in"))
      (node (ref "U2") (pin "29_3") (pinfunction "GND_29_3") (pintype "power_in"))
      (node (ref "U2") (pin "29_4") (pinfunction "GND_29_4") (pintype "power_in"))
      (node (ref "U2") (pin "29_5") (pinfunction "GND_29_5") (pintype "power_in"))
      (node (ref "U2") (pin "29_6") (pinfunction "GND_29_6") (pintype "power_in"))
      (node (ref "U2") (pin "29_7") (pinfunction "GND_29_7") (pintype "power_in"))
      (node (ref "U2") (pin "29_8") (pinfunction "GND_29_8") (pintype "power_in"))
      (node (ref "U2") (pin "29_9") (pinfunction "GND_29_9") (pintype "power_in"))
      (node (ref "U3") (pin "13") (pinfunction "GND_13") (pintype "power_in"))
      (node (ref "U4") (pin "1") (pinfunction "CTG_1") (pintype "power_in"))
      (node (ref "U4") (pin "4") (pinfunction "GND_4") (pintype "power_in"))
      (node (ref "U4") (pin "6") (pinfunction "QSTRT_6") (pintype "input"))
      (node (ref "U4") (pin "9") (pinfunction "EP_9") (pintype "power_in"))
    )
    (net (code "14") (name "GPIO8") (class "Default")
      (node (ref "R1") (pin "1") (pinfunction "1_1") (pintype "passive"))
      (node (ref "U2") (pin "10") (pinfunction "IO8_10") (pintype "bidirectional"))
    )
    (net (code "15") (name "I2C_PW") (class "Default")
      (node (ref "C1") (pin "1") (pinfunction "1_1") (pintype "passive"))
      (node (ref "C2") (pin "1") (pinfunction "1_1") (pintype "passive"))
      (node (ref "R1_PINH") (pin "2") (pinfunction "2_2") (pintype "passive"))
      (node (ref "R2_PINH") (pin "2") (pinfunction "2_2") (pintype "passive"))
      (node (ref "SENSOR2") (pin "2") (pinfunction "CSB_2") (pintype "input"))
      (node (ref "SENSOR2") (pin "6") (pinfunction "VDDIO_6") (pintype "power_in"))
      (node (ref "SENSOR2") (pin "8") (pinfunction "VDD_8") (pintype "power_in"))
      (node (ref "U2") (pin "17") (pinfunction "IO19_17") (pintype "bidirectional"))
    )
    (net (code "16") (name "INT_RTC") (class "Default")
      (node (ref "R1_PINH1") (pin "1") (pinfunction "1_1") (pintype "passive"))
      (node (ref "TP15") (pin "TP") (pinfunction "TP_TP") (pintype "input"))
      (node (ref "U2") (pin "8") (pinfunction "IO0_8") (pintype "bidirectional"))
      (node (ref "U3") (pin "3") (pinfunction "SQW/~{INT}_3") (pintype "output"))
    )
    (net (code "17") (name "IO{slash}BOOT") (class "Default")
      (node (ref "BOOT_BUTTON") (pin "3") (pinfunction "3_3") (pintype "passive"))
      (node (ref "BOOT_BUTTON") (pin "4") (pinfunction "4_4") (pintype "passive"))
      (node (ref "C6") (pin "1") (pinfunction "1_1") (pintype "passive"))
      (node (ref "R_BOOT") (pin "1") (pinfunction "1_1") (pintype "passive"))
      (node (ref "U2") (pin "15") (pinfunction "IO9_15") (pintype "bidirectional"))
    )
    (net (code "18") (name "IO{slash}CHANGE") (class "Default")
      (node (ref "C10") (pin "1") (pinfunction "1_1") (pintype "passive"))
      (node (ref "CHANGE_BUTTON") (pin "3") (pinfunction "3_3") (pintype "passive"))
      (node (ref "CHANGE_BUTTON") (pin "4") (pinfunction "4_4") (pintype "passive"))
      (node (ref "R_CHANGE") (pin "1") (pinfunction "1_1") (pintype "passive"))
      (node (ref "U2") (pin "23") (pinfunction "IO15_23") (pintype "bidirectional"))
    )
    (net (code "19") (name "MISO") (class "Default")
      (node (ref "D12") (pin "2") (pinfunction "2_2") (pintype "passive"))
      (node (ref "J4") (pin "P7") (pinfunction "DAT0_P7") (pintype "bidirectional"))
      (node (ref "R8") (pin "1") (pinfunction "1_1") (pintype "passive"))
      (node (ref "TP6") (pin "TP") (pinfunction "TP_TP") (pintype "input"))
      (node (ref "U1") (pin "2") (pinfunction "DO(IO1)_2") (pintype "bidirectional"))
      (node (ref "U2") (pin "27") (pinfunction "IO2_27") (pintype "bidirectional"))
    )
    (net (code "20") (name "MOSI") (class "Default")
      (node (ref "D11") (pin "2") (pinfunction "2_2") (pintype "passive"))
      (node (ref "J1") (pin "14") (pinfunction "14_14") (pintype "bidirectional"))
      (node (ref "J4") (pin "P3") (pinfunction "CMD_P3") (pintype "bidirectional"))
      (node (ref "R7") (pin "1") (pinfunction "1_1") (pintype "passive"))
      (node (ref "TP7") (pin "TP") (pinfunction "TP_TP") (pintype "input"))
      (node (ref "U1") (pin "5") (pinfunction "DI(IO0)_5") (pintype "bidirectional"))
      (node (ref "U2") (pin "7") (pinfunction "IO7_7") (pintype "bidirectional"))
    )
    (net (code "21") (name "Net-(CHG_LED-PadC)") (class "Default")
      (node (ref "CHG_LED") (pin "C") (pinfunction "C_C") (pintype "passive"))
      (node (ref "R1_BAT") (pin "1") (pinfunction "1_1") (pintype "passive"))
    )
    (net (code "22") (name "Net-(D2-CATHODE)") (class "Default")
      (node (ref "C1_BAT1") (pin "1") (pinfunction "1_1") (pintype "passive"))
      (node (ref "D2") (pin "1") (pinfunction "CATHODE_1") (pintype "bidirectional"))
      (node (ref "IC4") (pin "1") (pinfunction "VIN_1") (pintype "bidirectional"))
      (node (ref "IC4") (pin "3") (pinfunction "CE_3") (pintype "bidirectional"))
      (node (ref "Q1") (pin "2") (pinfunction "S_2") (pintype "bidirectional"))
    )
    (net (code "23") (name "Net-(D3-A)") (class "Default")
      (node (ref "C4") (pin "1") (pinfunction "1_1") (pintype "passive"))
      (node (ref "D3") (pin "2") (pinfunction "A_2") (pintype "bidirectional"))
      (node (ref "D4") (pin "1") (pinfunction "K_1") (pintype "bidirectional"))
    )
    (net (code "24") (name "Net-(D7-CATHODE)") (class "Default")
      (node (ref "D7") (pin "1") (pinfunction "CATHODE_1") (pintype "bidirectional"))
      (node (ref "R_CAPACITOR") (pin "1") (pinfunction "1_1") (pintype "passive"))
    )
    (net (code "25") (name "Net-(EPD_C1-Pad1)") (class "Default")
      (node (ref "EPD_C1") (pin "1") (pinfunction "1_1") (pintype "passive"))
      (node (ref "J1") (pin "4") (pinfunction "4_4") (pintype "bidirectional"))
    )
    (net (code "26") (name "Net-(EPD_C2-Pad1)") (class "Default")
      (node (ref "EPD_C2") (pin "1") (pinfunction "1_1") (pintype "passive"))
      (node (ref "J1") (pin "5") (pinfunction "5_5") (pintype "bidirectional"))
    )
    (net (code "27") (name "Net-(EPD_C6-Pad1)") (class "Default")
      (node (ref "EPD_C6") (pin "1") (pinfunction "1_1") (pintype "passive"))
      (node (ref "J1") (pin "18") (pinfunction "18_18") (pintype "bidirectional"))
    )
    (net (code "28") (name "Net-(EPD_C7-Pad1)") (class "Default")
      (node (ref "EPD_C7") (pin "1") (pinfunction "1_1") (pintype "passive"))
      (node (ref "J1") (pin "19") (pinfunction "19_19") (pintype "bidirectional"))
    )
    (net (code "29") (name "Net-(EPD_C8-Pad1)") (class "Default")
      (node (ref "EPD_C8") (pin "1") (pinfunction "1_1") (pintype "passive"))
      (node (ref "J1") (pin "20") (pinfunction "20_20") (pintype "bidirectional"))
    )
    (net (code "30") (name "Net-(EPD_C10-Pad1)") (class "Default")
      (node (ref "EPD_C10") (pin "1") (pinfunction "1_1") (pintype "passive"))
      (node (ref "J1") (pin "22") (pinfunction "22_22") (pintype "bidirectional"))
    )
    (net (code "31") (name "Net-(EPD_C12-Pad1)") (class "Default")
      (node (ref "EPD_C12") (pin "1") (pinfunction "1_1") (pintype "passive"))
      (node (ref "J1") (pin "24") (pinfunction "24_24") (pintype "bidirectional"))
    )
    (net (code "32") (name "Net-(IC1-CT)") (class "Default")
      (node (ref "C_DELAY") (pin "1") (pinfunction "1_1") (pintype "passive"))
      (node (ref "IC1") (pin "5") (pinfunction "CT_5") (pintype "bidirectional"))
    )
    (net (code "33") (name "Net-(J2-PadA5)") (class "Default")
      (node (ref "J2") (pin "A5") (pinfunction "A5_A5") (pintype "bidirectional"))
      (node (ref "R2-USB1") (pin "2") (pinfunction "2_2") (pintype "passive"))
    )
    (net (code "34") (name "Net-(J2-PadB5)") (class "Default")
      (node (ref "J2") (pin "B5") (pinfunction "B5_B5") (pintype "bidirectional"))
      (node (ref "R2-USB") (pin "1") (pinfunction "1_1") (pintype "passive"))
    )
    (net (code "35") (name "Net-(MCP73831-PROG)") (class "Default")
      (node (ref "MCP73831") (pin "5") (pinfunction "PROG_5") (pintype "input"))
      (node (ref "R2_BAT") (pin "2") (pinfunction "2_2") (pintype "passive"))
    )
    (net (code "36") (name "Net-(MCP73831-STAT)") (class "Default")
      (node (ref "MCP73831") (pin "1") (pinfunction "STAT_1") (pintype "output"))
      (node (ref "R1_BAT") (pin "2") (pinfunction "2_2") (pintype "passive"))
    )
    (net (code "37") (name "PREVGH") (class "Default")
      (node (ref "D5") (pin "1") (pinfunction "K_1") (pintype "bidirectional"))
      (node (ref "EPD_C9") (pin "1") (pinfunction "1_1") (pintype "passive"))
      (node (ref "J1") (pin "21") (pinfunction "21_21") (pintype "bidirectional"))
    )
    (net (code "38") (name "PREVGL") (class "Default")
      (node (ref "D4") (pin "2") (pinfunction "A_2") (pintype "bidirectional"))
      (node (ref "EPD_C11") (pin "1") (pinfunction "1_1") (pintype "passive"))
      (node (ref "J1") (pin "23") (pinfunction "23_23") (pintype "bidirectional"))
    )
    (net (code "39") (name "RESE") (class "Default")
      (node (ref "J1") (pin "3") (pinfunction "3_3") (pintype "bidirectional"))
      (node (ref "Q3") (pin "2") (pinfunction "S_2") (pintype "bidirectional"))
      (node (ref "R3") (pin "2") (pinfunction "2_2") (pintype "passive"))
    )
    (net (code "40") (name "RESE'") (class "Default")
      (node (ref "R2") (pin "2") (pinfunction "2_2") (pintype "passive"))
      (node (ref "R3") (pin "1") (pinfunction "1_1") (pintype "passive"))
      (node (ref "SJ1") (pin "2") (pinfunction "2_2") (pintype "passive"))
    )
    (net (code "41") (name "RESET") (class "Default")
      (node (ref "C5") (pin "1") (pinfunction "1_1") (pintype "passive"))
      (node (ref "IC1") (pin "1") (pinfunction "VOUT_1") (pintype "bidirectional"))
      (node (ref "RESET_BUTTON") (pin "3") (pinfunction "3_3") (pintype "passive"))
      (node (ref "RESET_BUTTON") (pin "4") (pinfunction "4_4") (pintype "passive"))
      (node (ref "R_RESET") (pin "1") (pinfunction "1_1") (pintype "passive"))
      (node (ref "U2") (pin "3") (pinfunction "EN_3") (pintype "input"))
    )
    (net (code "42") (name "RTC_RST") (class "Default")
      (node (ref "U2") (pin "16") (pinfunction "IO18_16") (pintype "bidirectional"))
      (node (ref "U3") (pin "4") (pinfunction "~{RST}_4") (pintype "input"))
    )
    (net (code "43") (name "RX") (class "Default")
      (node (ref "TP2") (pin "TP") (pinfunction "TP_TP") (pintype "input"))
      (node (ref "U2") (pin "24") (pinfunction "RXD0/GPIO17_24") (pintype "bidirectional"))
    )
    (net (code "44") (name "SCK") (class "Default")
      (node (ref "D10") (pin "2") (pinfunction "2_2") (pintype "passive"))
      (node (ref "J1") (pin "13") (pinfunction "13_13") (pintype "bidirectional"))
      (node (ref "J4") (pin "P5") (pinfunction "CLK_P5") (pintype "bidirectional"))
      (node (ref "R6") (pin "1") (pinfunction "1_1") (pintype "passive"))
      (node (ref "TP8") (pin "TP") (pinfunction "TP_TP") (pintype "input"))
      (node (ref "U1") (pin "6") (pinfunction "CLK_6") (pintype "input"))
      (node (ref "U2") (pin "6") (pinfunction "IO6_6") (pintype "bidirectional"))
    )
    (net (code "45") (name "SCL") (class "Default")
      (node (ref "J3") (pin "4") (pinfunction "4_4") (pintype "passive"))
      (node (ref "R2_PINH") (pin "1") (pinfunction "1_1") (pintype "passive"))
      (node (ref "SENSOR2") (pin "4") (pinfunction "SCK_4") (pintype "input"))
      (node (ref "U2") (pin "20") (pinfunction "IO22_20") (pintype "bidirectional"))
      (node (ref "U3") (pin "16") (pinfunction "SCL_16") (pintype "input"))
      (node (ref "U4") (pin "7") (pinfunction "SCL_7") (pintype "input"))
    )
    (net (code "46") (name "SDA") (class "Default")
      (node (ref "J3") (pin "3") (pinfunction "3_3") (pintype "passive"))
      (node (ref "R1_PINH") (pin "1") (pinfunction "1_1") (pintype "passive"))
      (node (ref "SENSOR2") (pin "3") (pinfunction "SDI_3") (pintype "bidirectional"))
      (node (ref "U2") (pin "19") (pinfunction "IO21_19") (pintype "bidirectional"))
      (node (ref "U3") (pin "15") (pinfunction "SDA_15") (pintype "bidirectional"))
      (node (ref "U4") (pin "8") (pinfunction "SDA_8") (pintype "bidirectional"))
    )
    (net (code "47") (name "SRC") (class "Default")
      (node (ref "C4") (pin "2") (pinfunction "2_2") (pintype "passive"))
      (node (ref "D5") (pin "2") (pinfunction "A_2") (pintype "bidirectional"))
      (node (ref "L1") (pin "1") (pinfunction "1_1") (pintype "passive"))
      (node (ref "Q3") (pin "3") (pinfunction "D_3") (pintype "bidirectional"))
    )
    (net (code "48") (name "SS_SD") (class "Default")
      (node (ref "D8") (pin "2") (pinfunction "2_2") (pintype "passive"))
      (node (ref "J4") (pin "P2") (pinfunction "CD/DAT3_P2") (pintype "bidirectional"))
      (node (ref "R10") (pin "1") (pinfunction "1_1") (pintype "passive"))
      (node (ref "U2") (pin "4") (pinfunction "IO4_4") (pintype "bidirectional"))
    )
    (net (code "49") (name "TX") (class "Default")
      (node (ref "TP1") (pin "TP") (pinfunction "TP_TP") (pintype "input"))
      (node (ref "U2") (pin "25") (pinfunction "TXD0/GPIO16_25") (pintype "bidirectional"))
    )
    (net (code "50") (name "USB_D+") (class "Default")
      (node (ref "D1") (pin "3") (pinfunction "I/O2_1_3") (pintype "bidirectional"))
      (node (ref "U2") (pin "14") (pinfunction "IO13_14") (pintype "bidirectional"))
    )
    (net (code "51") (name "USB_D-") (class "Default")
      (node (ref "D1") (pin "1") (pinfunction "I/O1_1_1") (pintype "bidirectional"))
      (node (ref "U2") (pin "13") (pinfunction "IO12_13") (pintype "bidirectional"))
    )
    (net (code "52") (name "VBAT") (class "Default")
      (node (ref "C2_BAT") (pin "1") (pinfunction "1_1") (pintype "passive"))
      (node (ref "MCP73831") (pin "3") (pinfunction "VBAT_3") (pintype "power_in"))
      (node (ref "Q1") (pin "3") (pinfunction "D_3") (pintype "bidirectional"))
      (node (ref "TP3") (pin "TP") (pinfunction "TP_TP") (pintype "input"))
      (node (ref "U4") (pin "2") (pinfunction "CELL_2") (pintype "power_in"))
      (node (ref "U4") (pin "3") (pinfunction "VDD_3") (pintype "power_in"))
    )
    (net (code "53") (name "VBUS") (class "Default")
      (node (ref "C1_BAT") (pin "1") (pinfunction "1_1") (pintype "passive"))
      (node (ref "C4_USB") (pin "1") (pinfunction "1_1") (pintype "passive"))
      (node (ref "C5_USB") (pin "1") (pinfunction "1_1") (pintype "passive"))
      (node (ref "CHG_LED") (pin "A") (pinfunction "A_A") (pintype "passive"))
      (node (ref "D1") (pin "5") (pinfunction "VBUS_5") (pintype "bidirectional"))
      (node (ref "D2") (pin "2") (pinfunction "ANODE_2") (pintype "bidirectional"))
      (node (ref "MCP73831") (pin "4") (pinfunction "VIN_4") (pintype "power_in"))
      (node (ref "PFMF.050.1") (pin "2") (pinfunction "2_2") (pintype "passive"))
      (node (ref "Q1") (pin "1") (pinfunction "G_1") (pintype "bidirectional"))
      (node (ref "R1_PWRUSB") (pin "2") (pinfunction "2_2") (pintype "passive"))
      (node (ref "TP14") (pin "TP") (pinfunction "TP_TP") (pintype "input"))
    )
    (net (code "54") (name "VRTC") (class "Default")
      (node (ref "C10_SUPERCAP") (pin "2") (pinfunction "2_2") (pintype "passive"))
      (node (ref "C8") (pin "1") (pinfunction "1_1") (pintype "passive"))
      (node (ref "R_CAPACITOR") (pin "2") (pinfunction "2_2") (pintype "passive"))
      (node (ref "U3") (pin "14") (pinfunction "VBAT_14") (pintype "power_in"))
    )
    (net (code "55") (name "VUSB") (class "Default")
      (node (ref "J2") (pin "A4") (pinfunction "A4_A4") (pintype "bidirectional"))
      (node (ref "J2") (pin "A9") (pinfunction "A9_A9") (pintype "bidirectional"))
      (node (ref "J2") (pin "B4") (pinfunction "B4_B4") (pintype "bidirectional"))
      (node (ref "J2") (pin "B9") (pinfunction "B9_B9") (pintype "bidirectional"))
      (node (ref "PFMF.050.1") (pin "1") (pinfunction "1_1") (pintype "passive"))
    )
    (net (code "56") (name "unconnected-(IC1-NC-Pad4)") (class "Default")
      (node (ref "IC1") (pin "4") (pinfunction "NC_4") (pintype "no_connect"))
    )
    (net (code "57") (name "unconnected-(IC4-NC-Pad4)") (class "Default")
      (node (ref "IC4") (pin "4") (pinfunction "NC_4") (pintype "no_connect"))
    )
    (net (code "58") (name "unconnected-(J1-Pad1)") (class "Default")
      (node (ref "J1") (pin "1") (pinfunction "1_1") (pintype "bidirectional"))
    )
    (net (code "59") (name "unconnected-(J1-Pad6)") (class "Default")
      (node (ref "J1") (pin "6") (pinfunction "6_6") (pintype "bidirectional"))
    )
    (net (code "60") (name "unconnected-(J1-Pad7)") (class "Default")
      (node (ref "J1") (pin "7") (pinfunction "7_7") (pintype "bidirectional"))
    )
    (net (code "61") (name "unconnected-(J2-PadA8)") (class "Default")
      (node (ref "J2") (pin "A8") (pinfunction "A8_A8") (pintype "bidirectional"))
    )
    (net (code "62") (name "unconnected-(J2-PadB8)") (class "Default")
      (node (ref "J2") (pin "B8") (pinfunction "B8_B8") (pintype "bidirectional"))
    )
    (net (code "63") (name "unconnected-(J4-DAT1-PadP8)") (class "Default")
      (node (ref "J4") (pin "P8") (pinfunction "DAT1_P8") (pintype "bidirectional"))
    )
    (net (code "64") (name "unconnected-(J4-DAT2-PadP1)") (class "Default")
      (node (ref "J4") (pin "P1") (pinfunction "DAT2_P1") (pintype "bidirectional"))
    )
    (net (code "65") (name "unconnected-(J4-DETECTION_1-PadS1)") (class "Default")
      (node (ref "J4") (pin "S1") (pinfunction "DETECTION_1_S1") (pintype "bidirectional"))
    )
    (net (code "66") (name "unconnected-(J4-DETECTION_2-PadS2)") (class "Default")
      (node (ref "J4") (pin "S2") (pinfunction "DETECTION_2_S2") (pintype "bidirectional"))
    )
    (net (code "67") (name "unconnected-(U2-NC-Pad22)") (class "Default")
      (node (ref "U2") (pin "22") (pinfunction "NC_22") (pintype "no_connect"))
    )
    (net (code "68") (name "unconnected-(U4-~{ALERT}-Pad5)") (class "Default")
      (node (ref "U4") (pin "5") (pinfunction "~{ALERT}_5") (pintype "output"))
    )
  )
)
